# OLED____2022-05-08.net
KiCad netlist of a schematic drawn in Altium Designer
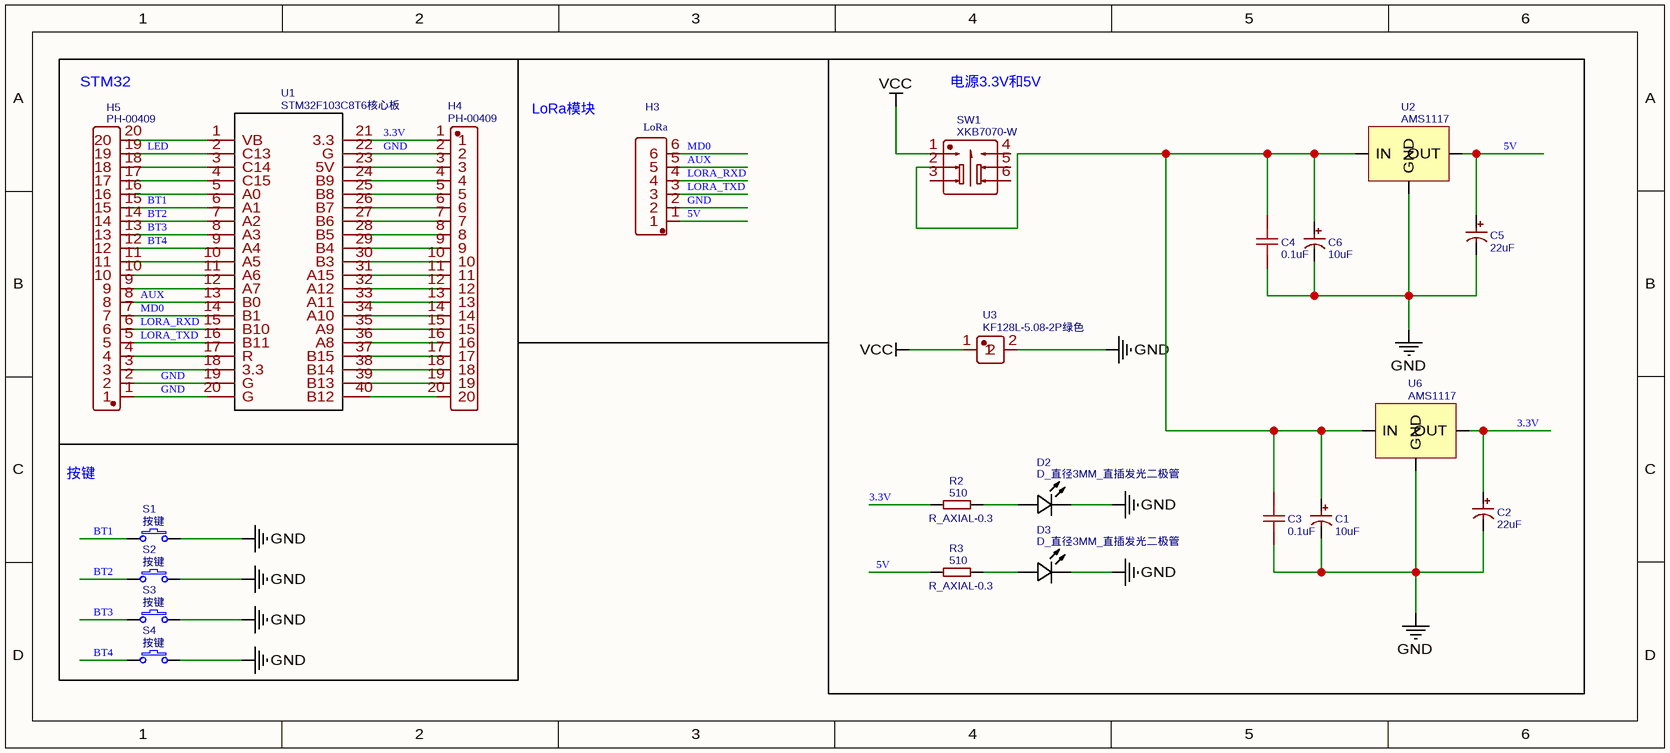
[diagram p0: OLED胸牌_主机_2022-05-08.schdoc]

(export (version "E")
  (design (tool "Eeschema 10.0.6"))
  (components
    (comp (ref "C1")
      (value "10uF")
      (fields
        (field (name "BOM_MANUFACTURER PART") "10uF 16V 3*5")
        (field (name "BOM_SUPPLIER PART") "C43798")
      )
      (libsource (lib "altium-import") (part "root_3_10uF_"))
    )
    (comp (ref "C2")
      (value "22uF")
      (fields
        (field (name "BOM_MANUFACTURER PART") "22uF 16V 4*5")
        (field (name "BOM_SUPPLIER PART") "C43800")
      )
      (libsource (lib "altium-import") (part "root_3_22uF_"))
    )
    (comp (ref "C3")
      (value "0.1uF")
      (fields
        (field (name "BOM_MANUFACTURER PART") "0603B104K500")
        (field (name "BOM_SUPPLIER PART") "C90807")
      )
      (libsource (lib "altium-import") (part "root_1_0.1uF_"))
    )
    (comp (ref "C4")
      (value "0.1uF")
      (fields
        (field (name "BOM_MANUFACTURER PART") "0603B104K500")
        (field (name "BOM_SUPPLIER PART") "C90807")
      )
      (libsource (lib "altium-import") (part "root_1_0.1uF_"))
    )
    (comp (ref "C5")
      (value "22uF")
      (fields
        (field (name "BOM_MANUFACTURER PART") "22uF 16V 4*5")
        (field (name "BOM_SUPPLIER PART") "C43800")
      )
      (libsource (lib "altium-import") (part "root_3_22uF_"))
    )
    (comp (ref "C6")
      (value "10uF")
      (fields
        (field (name "BOM_MANUFACTURER PART") "10uF 16V 3*5")
        (field (name "BOM_SUPPLIER PART") "C43798")
      )
      (libsource (lib "altium-import") (part "root_3_10uF_"))
    )
    (comp (ref "D2")
      (value "D_直径3MM_直插发光二极管")
      (fields (field (name "CONTRIBUTOR") "Jonejen"))
      (libsource (lib "altium-import") (part "root_1_D_直径3MM_直插发光二极管_"))
    )
    (comp (ref "D3")
      (value "D_直径3MM_直插发光二极管")
      (fields (field (name "CONTRIBUTOR") "Jonejen"))
      (libsource (lib "altium-import") (part "root_1_D_直径3MM_直插发光二极管_"))
    )
    (comp (ref "H3")
      (value "LoRa")
      (fields
        (field (name "BOM_MANUFACTURER PART") "220S-1*6P H=8.5MM Ytype Gold-plated")
        (field (name "BOM_SUPPLIER PART") "C124415")
        (field (name "CONTRIBUTOR") "LCSC")
      )
      (libsource (lib "altium-import") (part "root_2_LoRa_"))
    )
    (comp (ref "H4")
      (value "PH-00409")
      (fields (field (name "BOM_SUPPLIER PART") "C2685159") (field (name "CONTRIBUTOR") "LCSC"))
      (libsource (lib "altium-import") (part "root_0_PH-00409_"))
    )
    (comp (ref "H5")
      (value "PH-00409")
      (fields (field (name "BOM_SUPPLIER PART") "C2685159") (field (name "CONTRIBUTOR") "LCSC"))
      (libsource (lib "altium-import") (part "root_2_PH-00409_"))
    )
    (comp (ref "R2")
      (value "510")
      (fields
        (field (name "BOM_SUPPLIER PART") "C349179")
        (field (name "BOM_MANUFACTURER PART") "ECSF2512FR050K9")
        (field (name "CONTRIBUTOR") "CYZ139")
      )
      (libsource (lib "altium-import") (part "root_0_510_"))
    )
    (comp (ref "R3")
      (value "510")
      (fields
        (field (name "BOM_SUPPLIER PART") "C349179")
        (field (name "BOM_MANUFACTURER PART") "ECSF2512FR050K9")
        (field (name "CONTRIBUTOR") "CYZ139")
      )
      (libsource (lib "altium-import") (part "root_0_510_"))
    )
    (comp (ref "S1")
      (value "按键")
      (fields (field (name "CONTRIBUTOR") "jiaxiaoze"))
      (libsource (lib "altium-import") (part "root_0_按键_"))
    )
    (comp (ref "S2")
      (value "按键")
      (fields (field (name "CONTRIBUTOR") "jiaxiaoze"))
      (libsource (lib "altium-import") (part "root_0_按键_"))
    )
    (comp (ref "S3")
      (value "按键")
      (fields (field (name "CONTRIBUTOR") "jiaxiaoze"))
      (libsource (lib "altium-import") (part "root_0_按键_"))
    )
    (comp (ref "S4")
      (value "按键")
      (fields (field (name "CONTRIBUTOR") "jiaxiaoze"))
      (libsource (lib "altium-import") (part "root_0_按键_"))
    )
    (comp (ref "SW1")
      (value "XKB7070-W")
      (fields (field (name "BOM_SUPPLIER PART") "C318864") (field (name "CONTRIBUTOR") "LCSC"))
      (libsource (lib "altium-import") (part "root_0_XKB7070-W_"))
    )
    (comp (ref "U1")
      (value "STM32F103C8T6核心板")
      (fields (field (name "CONTRIBUTOR") "yuleiweiheluo"))
      (libsource (lib "altium-import") (part "root_0_STM32F103C8T6核心板_"))
    )
    (comp (ref "U2")
      (value "AMS1117")
      (fields (field (name "CONTRIBUTOR") "zhangxiaobudong"))
      (libsource (lib "altium-import") (part "root_0_AMS1117_"))
    )
    (comp (ref "U3")
      (value "KF128L-5.08-2P绿色")
      (fields (field (name "BOM_SUPPLIER PART") "C2916952") (field (name "CONTRIBUTOR") "LCSC"))
      (libsource (lib "altium-import") (part "root_0_KF128L-5.08-2P绿色_"))
    )
    (comp (ref "U6")
      (value "AMS1117")
      (fields (field (name "CONTRIBUTOR") "zhangxiaobudong"))
      (libsource (lib "altium-import") (part "root_0_AMS1117_"))
    )
  )
  (nets
    (net (code "1") (name "/3.3V") (class "Default")
      (node (ref "C2") (pin "1") (pinfunction "1_1") (pintype "passive"))
      (node (ref "H4") (pin "1") (pinfunction "1_1") (pintype "passive"))
      (node (ref "R2") (pin "1") (pinfunction "1_1") (pintype "passive"))
      (node (ref "U1") (pin "21") (pinfunction "3.3_21") (pintype "passive"))
      (node (ref "U6") (pin "2") (pinfunction "OUT_2") (pintype "passive"))
    )
    (net (code "2") (name "/5V") (class "Default")
      (node (ref "C5") (pin "1") (pinfunction "1_1") (pintype "passive"))
      (node (ref "H3") (pin "1") (pinfunction "1_1") (pintype "passive"))
      (node (ref "R3") (pin "1") (pinfunction "1_1") (pintype "passive"))
      (node (ref "U2") (pin "2") (pinfunction "OUT_2") (pintype "passive"))
    )
    (net (code "3") (name "/AUX") (class "Default")
      (node (ref "H3") (pin "5") (pinfunction "5_5") (pintype "passive"))
      (node (ref "H5") (pin "8") (pinfunction "8_8") (pintype "passive"))
      (node (ref "U1") (pin "13") (pinfunction "B0_13") (pintype "passive"))
    )
    (net (code "4") (name "/BT1") (class "Default")
      (node (ref "H5") (pin "15") (pinfunction "15_15") (pintype "passive"))
      (node (ref "S1") (pin "1") (pinfunction "1_1") (pintype "passive"))
      (node (ref "U1") (pin "6") (pinfunction "A1_6") (pintype "passive"))
    )
    (net (code "5") (name "/BT2") (class "Default")
      (node (ref "H5") (pin "14") (pinfunction "14_14") (pintype "passive"))
      (node (ref "S2") (pin "1") (pinfunction "1_1") (pintype "passive"))
      (node (ref "U1") (pin "7") (pinfunction "A2_7") (pintype "passive"))
    )
    (net (code "6") (name "/BT3") (class "Default")
      (node (ref "H5") (pin "13") (pinfunction "13_13") (pintype "passive"))
      (node (ref "S3") (pin "1") (pinfunction "1_1") (pintype "passive"))
      (node (ref "U1") (pin "8") (pinfunction "A3_8") (pintype "passive"))
    )
    (net (code "7") (name "/BT4") (class "Default")
      (node (ref "H5") (pin "12") (pinfunction "12_12") (pintype "passive"))
      (node (ref "S4") (pin "1") (pinfunction "1_1") (pintype "passive"))
      (node (ref "U1") (pin "9") (pinfunction "A4_9") (pintype "passive"))
    )
    (net (code "8") (name "/LED") (class "Default")
      (node (ref "H5") (pin "19") (pinfunction "19_19") (pintype "passive"))
      (node (ref "U1") (pin "2") (pinfunction "C13_2") (pintype "passive"))
    )
    (net (code "9") (name "/LORA_RXD") (class "Default")
      (node (ref "H3") (pin "4") (pinfunction "4_4") (pintype "passive"))
      (node (ref "H5") (pin "6") (pinfunction "6_6") (pintype "passive"))
      (node (ref "U1") (pin "15") (pinfunction "B10_15") (pintype "passive"))
    )
    (net (code "10") (name "/LORA_TXD") (class "Default")
      (node (ref "H3") (pin "3") (pinfunction "3_3") (pintype "passive"))
      (node (ref "H5") (pin "5") (pinfunction "5_5") (pintype "passive"))
      (node (ref "U1") (pin "16") (pinfunction "B11_16") (pintype "passive"))
    )
    (net (code "11") (name "/MD0") (class "Default")
      (node (ref "H3") (pin "6") (pinfunction "6_6") (pintype "passive"))
      (node (ref "H5") (pin "7") (pinfunction "7_7") (pintype "passive"))
      (node (ref "U1") (pin "14") (pinfunction "B1_14") (pintype "passive"))
    )
    (net (code "12") (name "GND") (class "Default")
      (node (ref "C1") (pin "2") (pinfunction "2_2") (pintype "passive"))
      (node (ref "C2") (pin "2") (pinfunction "2_2") (pintype "passive"))
      (node (ref "C3") (pin "1") (pinfunction "1_1") (pintype "passive"))
      (node (ref "C4") (pin "1") (pinfunction "1_1") (pintype "passive"))
      (node (ref "C5") (pin "2") (pinfunction "2_2") (pintype "passive"))
      (node (ref "C6") (pin "2") (pinfunction "2_2") (pintype "passive"))
      (node (ref "D2") (pin "2") (pinfunction "K_2") (pintype "passive"))
      (node (ref "D3") (pin "2") (pinfunction "K_2") (pintype "passive"))
      (node (ref "H3") (pin "2") (pinfunction "2_2") (pintype "passive"))
      (node (ref "H4") (pin "2") (pinfunction "2_2") (pintype "passive"))
      (node (ref "H5") (pin "1") (pinfunction "1_1") (pintype "passive"))
      (node (ref "H5") (pin "2") (pinfunction "2_2") (pintype "passive"))
      (node (ref "S1") (pin "3") (pinfunction "3_3") (pintype "passive"))
      (node (ref "S2") (pin "3") (pinfunction "3_3") (pintype "passive"))
      (node (ref "S3") (pin "3") (pinfunction "3_3") (pintype "passive"))
      (node (ref "S4") (pin "3") (pinfunction "3_3") (pintype "passive"))
      (node (ref "U1") (pin "19") (pinfunction "G_19") (pintype "passive"))
      (node (ref "U1") (pin "20") (pinfunction "G_20") (pintype "passive"))
      (node (ref "U1") (pin "22") (pinfunction "G_22") (pintype "passive"))
      (node (ref "U2") (pin "1") (pinfunction "GND_1") (pintype "passive"))
      (node (ref "U3") (pin "2") (pinfunction "2_2") (pintype "passive"))
      (node (ref "U6") (pin "1") (pinfunction "GND_1") (pintype "passive"))
    )
    (net (code "13") (name "Net-(D2-A)") (class "Default")
      (node (ref "D2") (pin "1") (pinfunction "A_1") (pintype "passive"))
      (node (ref "R2") (pin "2") (pinfunction "2_2") (pintype "passive"))
    )
    (net (code "14") (name "Net-(D3-A)") (class "Default")
      (node (ref "D3") (pin "1") (pinfunction "A_1") (pintype "passive"))
      (node (ref "R3") (pin "2") (pinfunction "2_2") (pintype "passive"))
    )
    (net (code "15") (name "Net-(H5-Pad3)") (class "Default")
      (node (ref "H5") (pin "3") (pinfunction "3_3") (pintype "passive"))
      (node (ref "U1") (pin "18") (pinfunction "3.3_18") (pintype "passive"))
    )
    (net (code "16") (name "Net-(U1-5V)") (class "Default")
      (node (ref "H4") (pin "3") (pinfunction "3_3") (pintype "passive"))
      (node (ref "U1") (pin "23") (pinfunction "5V_23") (pintype "passive"))
    )
    (net (code "17") (name "Net-(U1-A0)") (class "Default")
      (node (ref "H5") (pin "16") (pinfunction "16_16") (pintype "passive"))
      (node (ref "U1") (pin "5") (pinfunction "A0_5") (pintype "passive"))
    )
    (net (code "18") (name "Net-(U1-A5)") (class "Default")
      (node (ref "H5") (pin "11") (pinfunction "11_11") (pintype "passive"))
      (node (ref "U1") (pin "10") (pinfunction "A5_10") (pintype "passive"))
    )
    (net (code "19") (name "Net-(U1-A6)") (class "Default")
      (node (ref "H5") (pin "10") (pinfunction "10_10") (pintype "passive"))
      (node (ref "U1") (pin "11") (pinfunction "A6_11") (pintype "passive"))
    )
    (net (code "20") (name "Net-(U1-A7)") (class "Default")
      (node (ref "H5") (pin "9") (pinfunction "9_9") (pintype "passive"))
      (node (ref "U1") (pin "12") (pinfunction "A7_12") (pintype "passive"))
    )
    (net (code "21") (name "Net-(U1-A8)") (class "Default")
      (node (ref "H4") (pin "16") (pinfunction "16_16") (pintype "passive"))
      (node (ref "U1") (pin "36") (pinfunction "A8_36") (pintype "passive"))
    )
    (net (code "22") (name "Net-(U1-A9)") (class "Default")
      (node (ref "H4") (pin "15") (pinfunction "15_15") (pintype "passive"))
      (node (ref "U1") (pin "35") (pinfunction "A9_35") (pintype "passive"))
    )
    (net (code "23") (name "Net-(U1-A10)") (class "Default")
      (node (ref "H4") (pin "14") (pinfunction "14_14") (pintype "passive"))
      (node (ref "U1") (pin "34") (pinfunction "A10_34") (pintype "passive"))
    )
    (net (code "24") (name "Net-(U1-A11)") (class "Default")
      (node (ref "H4") (pin "13") (pinfunction "13_13") (pintype "passive"))
      (node (ref "U1") (pin "33") (pinfunction "A11_33") (pintype "passive"))
    )
    (net (code "25") (name "Net-(U1-A12)") (class "Default")
      (node (ref "H4") (pin "12") (pinfunction "12_12") (pintype "passive"))
      (node (ref "U1") (pin "32") (pinfunction "A12_32") (pintype "passive"))
    )
    (net (code "26") (name "Net-(U1-A15)") (class "Default")
      (node (ref "H4") (pin "11") (pinfunction "11_11") (pintype "passive"))
      (node (ref "U1") (pin "31") (pinfunction "A15_31") (pintype "passive"))
    )
    (net (code "27") (name "Net-(U1-B3)") (class "Default")
      (node (ref "H4") (pin "10") (pinfunction "10_10") (pintype "passive"))
      (node (ref "U1") (pin "30") (pinfunction "B3_30") (pintype "passive"))
    )
    (net (code "28") (name "Net-(U1-B4)") (class "Default")
      (node (ref "H4") (pin "9") (pinfunction "9_9") (pintype "passive"))
      (node (ref "U1") (pin "29") (pinfunction "B4_29") (pintype "passive"))
    )
    (net (code "29") (name "Net-(U1-B5)") (class "Default")
      (node (ref "H4") (pin "8") (pinfunction "8_8") (pintype "passive"))
      (node (ref "U1") (pin "28") (pinfunction "B5_28") (pintype "passive"))
    )
    (net (code "30") (name "Net-(U1-B6)") (class "Default")
      (node (ref "H4") (pin "7") (pinfunction "7_7") (pintype "passive"))
      (node (ref "U1") (pin "27") (pinfunction "B6_27") (pintype "passive"))
    )
    (net (code "31") (name "Net-(U1-B7)") (class "Default")
      (node (ref "H4") (pin "6") (pinfunction "6_6") (pintype "passive"))
      (node (ref "U1") (pin "26") (pinfunction "B7_26") (pintype "passive"))
    )
    (net (code "32") (name "Net-(U1-B8)") (class "Default")
      (node (ref "H4") (pin "5") (pinfunction "5_5") (pintype "passive"))
      (node (ref "U1") (pin "25") (pinfunction "B8_25") (pintype "passive"))
    )
    (net (code "33") (name "Net-(U1-B9)") (class "Default")
      (node (ref "H4") (pin "4") (pinfunction "4_4") (pintype "passive"))
      (node (ref "U1") (pin "24") (pinfunction "B9_24") (pintype "passive"))
    )
    (net (code "34") (name "Net-(U1-B12)") (class "Default")
      (node (ref "H4") (pin "20") (pinfunction "20_20") (pintype "passive"))
      (node (ref "U1") (pin "40") (pinfunction "B12_40") (pintype "passive"))
    )
    (net (code "35") (name "Net-(U1-B13)") (class "Default")
      (node (ref "H4") (pin "19") (pinfunction "19_19") (pintype "passive"))
      (node (ref "U1") (pin "39") (pinfunction "B13_39") (pintype "passive"))
    )
    (net (code "36") (name "Net-(U1-B14)") (class "Default")
      (node (ref "H4") (pin "18") (pinfunction "18_18") (pintype "passive"))
      (node (ref "U1") (pin "38") (pinfunction "B14_38") (pintype "passive"))
    )
    (net (code "37") (name "Net-(U1-B15)") (class "Default")
      (node (ref "H4") (pin "17") (pinfunction "17_17") (pintype "passive"))
      (node (ref "U1") (pin "37") (pinfunction "B15_37") (pintype "passive"))
    )
    (net (code "38") (name "Net-(U1-C14)") (class "Default")
      (node (ref "H5") (pin "18") (pinfunction "18_18") (pintype "passive"))
      (node (ref "U1") (pin "3") (pinfunction "C14_3") (pintype "passive"))
    )
    (net (code "39") (name "Net-(U1-C15)") (class "Default")
      (node (ref "H5") (pin "17") (pinfunction "17_17") (pintype "passive"))
      (node (ref "U1") (pin "4") (pinfunction "C15_4") (pintype "passive"))
    )
    (net (code "40") (name "Net-(U1-R)") (class "Default")
      (node (ref "H5") (pin "4") (pinfunction "4_4") (pintype "passive"))
      (node (ref "U1") (pin "17") (pinfunction "R_17") (pintype "passive"))
    )
    (net (code "41") (name "Net-(U1-VB)") (class "Default")
      (node (ref "H5") (pin "20") (pinfunction "20_20") (pintype "passive"))
      (node (ref "U1") (pin "1") (pinfunction "VB_1") (pintype "passive"))
    )
    (net (code "42") (name "Net-(U2-IN)") (class "Default")
      (node (ref "C1") (pin "1") (pinfunction "1_1") (pintype "passive"))
      (node (ref "C3") (pin "2") (pinfunction "2_2") (pintype "passive"))
      (node (ref "C4") (pin "2") (pinfunction "2_2") (pintype "passive"))
      (node (ref "C6") (pin "1") (pinfunction "1_1") (pintype "passive"))
      (node (ref "SW1") (pin "2") (pinfunction "2_2") (pintype "passive"))
      (node (ref "U2") (pin "3") (pinfunction "IN_3") (pintype "passive"))
      (node (ref "U6") (pin "3") (pinfunction "IN_3") (pintype "passive"))
    )
    (net (code "43") (name "VCC") (class "Default")
      (node (ref "SW1") (pin "1") (pinfunction "1_1") (pintype "passive"))
      (node (ref "U3") (pin "1") (pinfunction "1_1") (pintype "passive"))
    )
    (net (code "44") (name "unconnected-(SW1-Pad3)") (class "Default")
      (node (ref "SW1") (pin "3") (pinfunction "3_3") (pintype "passive"))
    )
    (net (code "45") (name "unconnected-(SW1-Pad4)") (class "Default")
      (node (ref "SW1") (pin "4") (pinfunction "4_4") (pintype "passive"))
    )
    (net (code "46") (name "unconnected-(SW1-Pad5)") (class "Default")
      (node (ref "SW1") (pin "5") (pinfunction "5_5") (pintype "passive"))
    )
    (net (code "47") (name "unconnected-(SW1-Pad6)") (class "Default")
      (node (ref "SW1") (pin "6") (pinfunction "6_6") (pintype "passive"))
    )
  )
)
